# Puzzle_Digital_light_sensor_v0_9b.net
KiCad netlist of a schematic drawn in EAGLE
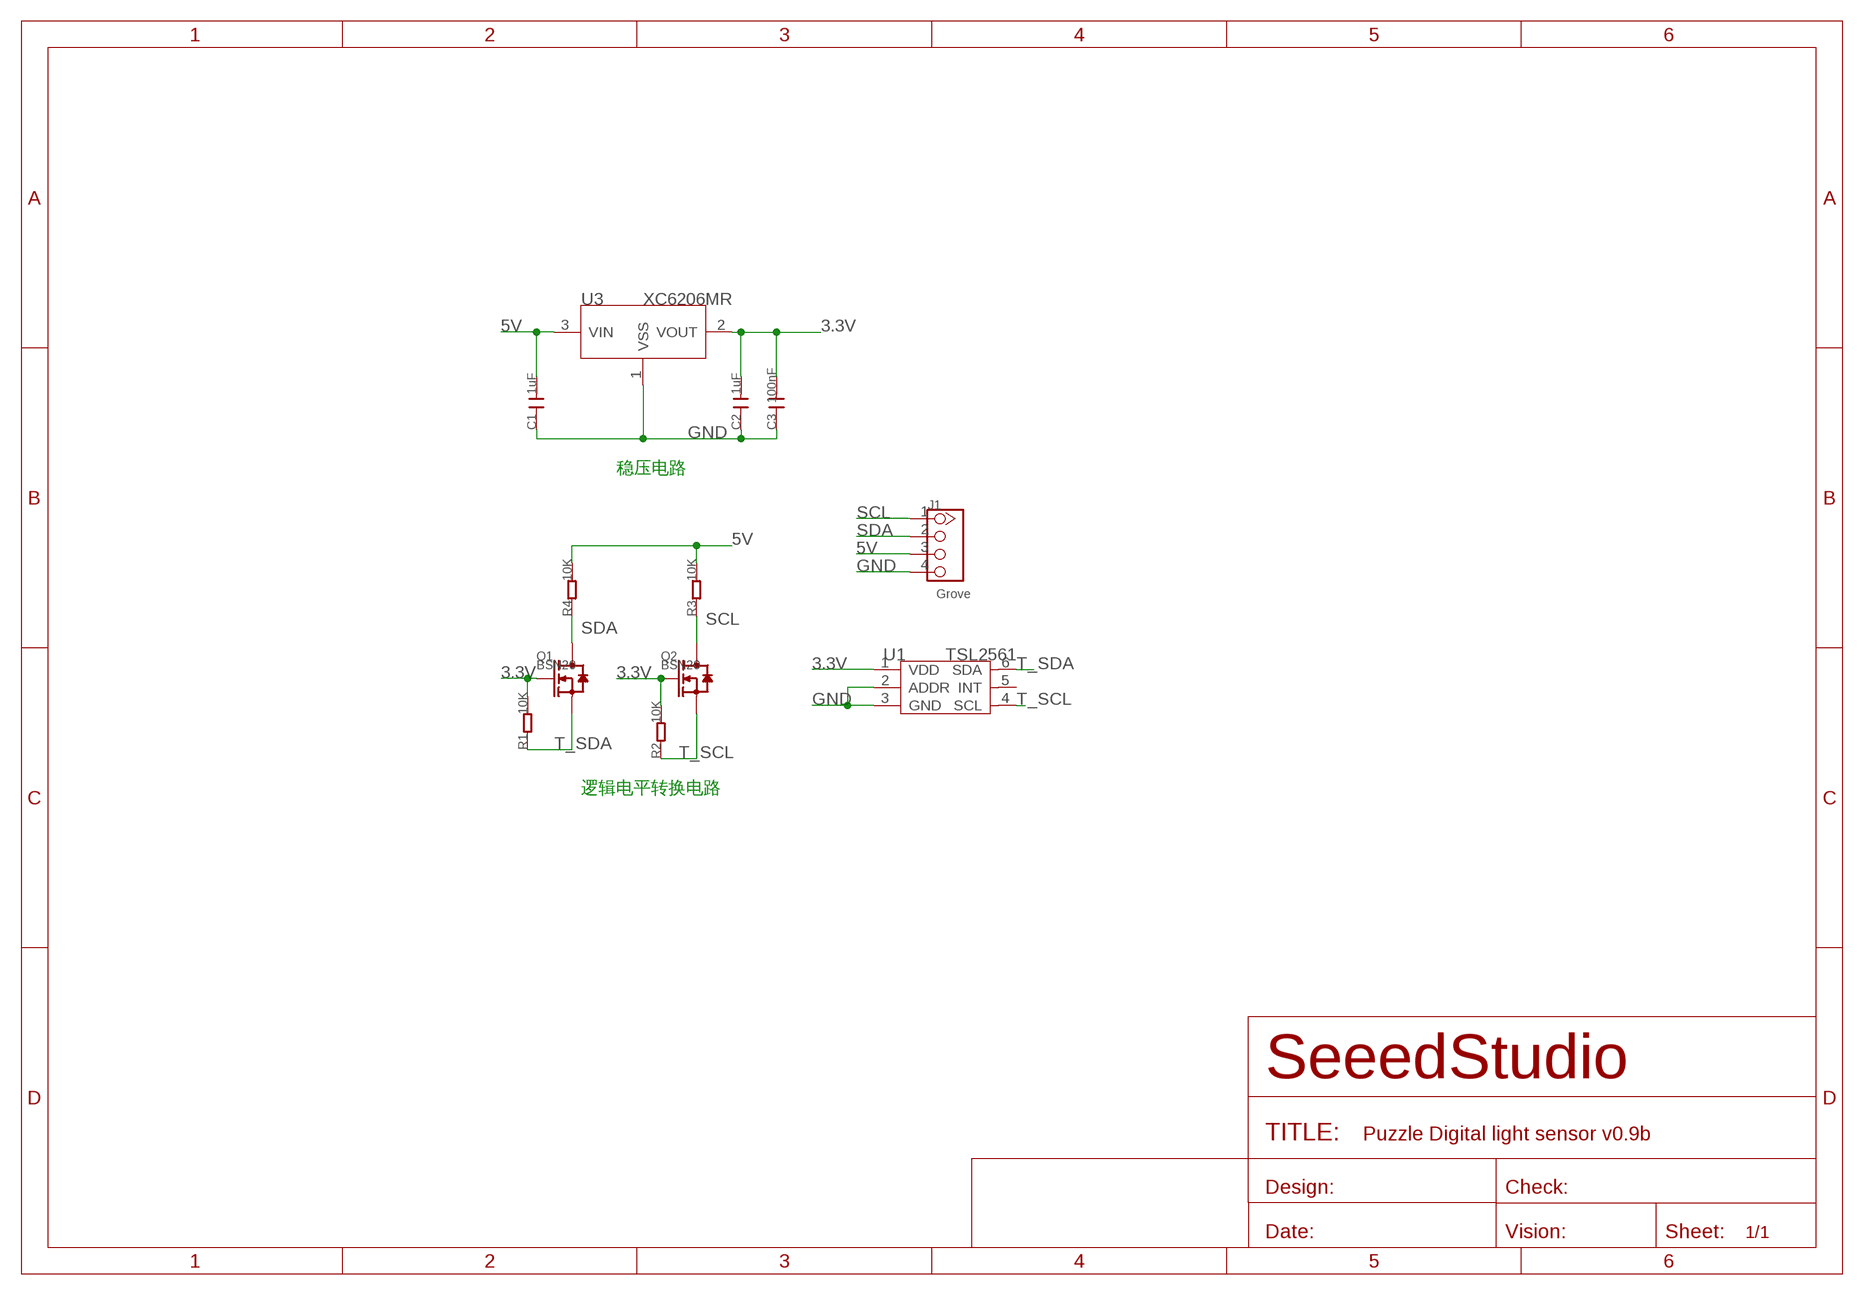
[diagram p0: schematic, sheet 1]

(export (version "E")
  (design (tool "Eeschema 10.0.6"))
  (components
    (comp (ref "C1")
      (value "1uF")
      (footprint "eagle-import:C0603")
      (libsource (lib "eagle-import") (part "C-0603"))
    )
    (comp (ref "C2")
      (value "1uF")
      (footprint "eagle-import:C0603")
      (libsource (lib "eagle-import") (part "C-0603"))
    )
    (comp (ref "C3")
      (value "100nF")
      (footprint "eagle-import:C0603")
      (libsource (lib "eagle-import") (part "C-0603"))
    )
    (comp (ref "J1")
      (value "Grove")
      (footprint "eagle-import:4P-2.0")
      (libsource (lib "eagle-import") (part "TWIG-4P-2.0-2.0"))
    )
    (comp (ref "Q1")
      (value "BSN20")
      (footprint "eagle-import:SOT23")
      (libsource (lib "eagle-import") (part "MOSFET-N'SOT23'"))
    )
    (comp (ref "Q2")
      (value "BSN20")
      (footprint "eagle-import:SOT23")
      (libsource (lib "eagle-import") (part "MOSFET-N'SOT23'"))
    )
    (comp (ref "R1")
      (value "10K")
      (footprint "eagle-import:R0603")
      (libsource (lib "eagle-import") (part "R-0603"))
    )
    (comp (ref "R2")
      (value "10K")
      (footprint "eagle-import:R0603")
      (libsource (lib "eagle-import") (part "R-0603"))
    )
    (comp (ref "R3")
      (value "10K")
      (footprint "eagle-import:R0603")
      (libsource (lib "eagle-import") (part "R-0603"))
    )
    (comp (ref "R4")
      (value "10K")
      (footprint "eagle-import:R0603")
      (libsource (lib "eagle-import") (part "R-0603"))
    )
    (comp (ref "U1")
      (value "TSL2561")
      (footprint "eagle-import:TMB-6")
      (libsource (lib "eagle-import") (part "TSL2561T"))
    )
    (comp (ref "U3")
      (value "XC6206MR")
      (footprint "eagle-import:SOT23")
      (libsource (lib "eagle-import") (part "XC6206MR"))
    )
  )
  (nets
    (net (code "1") (name "/3.3V") (class "Default")
      (node (ref "C2") (pin "2") (pinfunction "2_2") (pintype "passive"))
      (node (ref "C3") (pin "2") (pinfunction "2_2") (pintype "passive"))
      (node (ref "Q1") (pin "1") (pinfunction "G_1") (pintype "passive"))
      (node (ref "Q2") (pin "1") (pinfunction "G_1") (pintype "passive"))
      (node (ref "R1") (pin "2") (pinfunction "2_2") (pintype "passive"))
      (node (ref "R2") (pin "2") (pinfunction "2_2") (pintype "passive"))
      (node (ref "U1") (pin "1") (pinfunction "VDD_1") (pintype "power_in"))
      (node (ref "U3") (pin "2") (pinfunction "VOUT_2") (pintype "output"))
    )
    (net (code "2") (name "/5V") (class "Default")
      (node (ref "C1") (pin "2") (pinfunction "2_2") (pintype "passive"))
      (node (ref "J1") (pin "3") (pinfunction "3_3") (pintype "bidirectional"))
      (node (ref "R3") (pin "2") (pinfunction "2_2") (pintype "passive"))
      (node (ref "R4") (pin "2") (pinfunction "2_2") (pintype "passive"))
      (node (ref "U3") (pin "3") (pinfunction "VIN_3") (pintype "input"))
    )
    (net (code "3") (name "/GND") (class "Default")
      (node (ref "C1") (pin "1") (pinfunction "1_1") (pintype "passive"))
      (node (ref "C2") (pin "1") (pinfunction "1_1") (pintype "passive"))
      (node (ref "C3") (pin "1") (pinfunction "1_1") (pintype "passive"))
      (node (ref "J1") (pin "4") (pinfunction "4_4") (pintype "bidirectional"))
      (node (ref "U1") (pin "2") (pinfunction "ADDR_2") (pintype "input"))
      (node (ref "U1") (pin "3") (pinfunction "GND_3") (pintype "power_in"))
      (node (ref "U3") (pin "1") (pinfunction "VSS_1") (pintype "power_in"))
    )
    (net (code "4") (name "/SCL") (class "Default")
      (node (ref "J1") (pin "1") (pinfunction "1_1") (pintype "bidirectional"))
      (node (ref "Q2") (pin "3") (pinfunction "D_3") (pintype "passive"))
      (node (ref "R3") (pin "1") (pinfunction "1_1") (pintype "passive"))
    )
    (net (code "5") (name "/SDA") (class "Default")
      (node (ref "J1") (pin "2") (pinfunction "2_2") (pintype "bidirectional"))
      (node (ref "Q1") (pin "3") (pinfunction "D_3") (pintype "passive"))
      (node (ref "R4") (pin "1") (pinfunction "1_1") (pintype "passive"))
    )
    (net (code "6") (name "/T_SCL") (class "Default")
      (node (ref "Q2") (pin "2") (pinfunction "S_2") (pintype "passive"))
      (node (ref "R2") (pin "1") (pinfunction "1_1") (pintype "passive"))
      (node (ref "U1") (pin "4") (pinfunction "SCL_4") (pintype "input"))
    )
    (net (code "7") (name "/T_SDA") (class "Default")
      (node (ref "Q1") (pin "2") (pinfunction "S_2") (pintype "passive"))
      (node (ref "R1") (pin "1") (pinfunction "1_1") (pintype "passive"))
      (node (ref "U1") (pin "6") (pinfunction "SDA_6") (pintype "bidirectional"))
    )
    (net (code "8") (name "unconnected-(U1-INT-Pad5)") (class "Default")
      (node (ref "U1") (pin "5") (pinfunction "INT_5") (pintype "output"))
    )
  )
)
